# XBee_v1.net
KiCad netlist of a schematic drawn in EAGLE
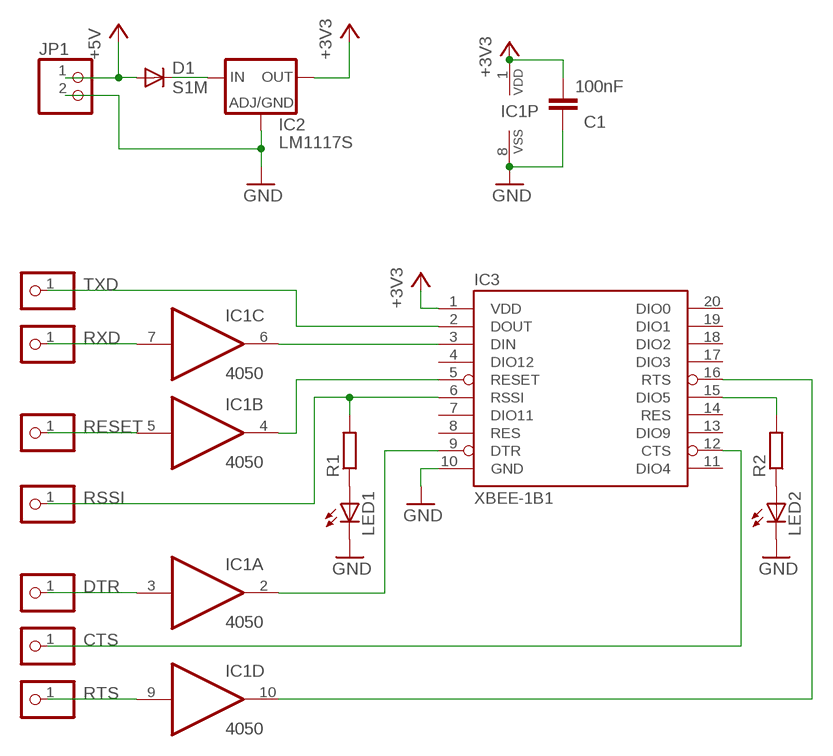
[diagram p0: schematic, sheet 1]

(export (version "E")
  (design (tool "Eeschema 10.0.6"))
  (components
    (comp (ref "C1")
      (value "100nF")
      (footprint "eagle-import:C0805K")
      (libsource (lib "eagle-import") (part "C-EUC0805K"))
    )
    (comp (ref "D1")
      (value "S1M")
      (footprint "eagle-import:DO-214AC")
      (libsource (lib "eagle-import") (part "S1M"))
    )
    (comp (ref "IC1")
      (value "4050")
      (footprint "eagle-import:SO16")
      (libsource (lib "eagle-import") (part "4050D"))
    )
    (comp (ref "IC2")
      (value "LM1117S")
      (footprint "eagle-import:SOT223")
      (libsource (lib "eagle-import") (part "LM1117S"))
    )
    (comp (ref "IC3")
      (value "XBEE-1B1")
      (footprint "eagle-import:XBEE-1")
      (libsource (lib "eagle-import") (part "XBEE-1B1"))
    )
    (comp (ref "JP1")
      (value "PINHD-1X2")
      (footprint "eagle-import:1X02")
      (libsource (lib "eagle-import") (part "PINHD-1X2"))
    )
    (comp (ref "JP2")
      (value "TXD")
      (footprint "eagle-import:1X01")
      (libsource (lib "eagle-import") (part "PINHD-1X1"))
    )
    (comp (ref "JP3")
      (value "RXD")
      (footprint "eagle-import:1X01")
      (libsource (lib "eagle-import") (part "PINHD-1X1"))
    )
    (comp (ref "JP4")
      (value "RST")
      (footprint "eagle-import:1X01")
      (libsource (lib "eagle-import") (part "PINHD-1X1"))
    )
    (comp (ref "JP5")
      (value "RSSI")
      (footprint "eagle-import:1X01")
      (libsource (lib "eagle-import") (part "PINHD-1X1"))
    )
    (comp (ref "JP6")
      (value "DTR")
      (footprint "eagle-import:1X01")
      (libsource (lib "eagle-import") (part "PINHD-1X1"))
    )
    (comp (ref "JP7")
      (value "CTS")
      (footprint "eagle-import:1X01")
      (libsource (lib "eagle-import") (part "PINHD-1X1"))
    )
    (comp (ref "JP8")
      (value "RTS")
      (footprint "eagle-import:1X01")
      (libsource (lib "eagle-import") (part "PINHD-1X1"))
    )
    (comp (ref "LED1")
      (value "LED3MM")
      (footprint "eagle-import:LED3MM")
      (libsource (lib "eagle-import") (part "LED3MM"))
    )
    (comp (ref "LED2")
      (value "LED3MM")
      (footprint "eagle-import:LED3MM")
      (libsource (lib "eagle-import") (part "LED3MM"))
    )
    (comp (ref "R1")
      (value "R-EU_R0805")
      (footprint "eagle-import:R0805")
      (libsource (lib "eagle-import") (part "R-EU_R0805"))
    )
    (comp (ref "R2")
      (value "R-EU_R0805")
      (footprint "eagle-import:R0805")
      (libsource (lib "eagle-import") (part "R-EU_R0805"))
    )
  )
  (nets
    (net (code "1") (name "+3V3") (class "Default")
      (node (ref "C1") (pin "2") (pinfunction "2_2") (pintype "passive"))
      (node (ref "IC1") (pin "1") (pinfunction "VDD_1") (pintype "power_in"))
      (node (ref "IC2") (pin "2") (pinfunction "OUT_2") (pintype "passive"))
      (node (ref "IC2") (pin "4") (pinfunction "OUT_4") (pintype "passive"))
      (node (ref "IC3") (pin "1") (pinfunction "VDD_1") (pintype "power_in"))
    )
    (net (code "2") (name "+5V") (class "Default")
      (node (ref "D1") (pin "A") (pinfunction "A_A") (pintype "passive"))
      (node (ref "JP1") (pin "1") (pinfunction "1_1") (pintype "passive"))
    )
    (net (code "3") (name "/CTS") (class "Default")
      (node (ref "IC3") (pin "12") (pinfunction "CTS_12") (pintype "output"))
      (node (ref "JP7") (pin "1") (pinfunction "1_1") (pintype "passive"))
    )
    (net (code "4") (name "/DTR") (class "Default")
      (node (ref "IC1") (pin "3") (pinfunction "I_3") (pintype "input"))
      (node (ref "JP6") (pin "1") (pinfunction "1_1") (pintype "passive"))
    )
    (net (code "5") (name "/RESET") (class "Default")
      (node (ref "IC1") (pin "5") (pinfunction "I_5") (pintype "input"))
      (node (ref "JP4") (pin "1") (pinfunction "1_1") (pintype "passive"))
    )
    (net (code "6") (name "/RSSI") (class "Default")
      (node (ref "IC3") (pin "6") (pinfunction "RSSI_6") (pintype "bidirectional"))
      (node (ref "JP5") (pin "1") (pinfunction "1_1") (pintype "passive"))
      (node (ref "R1") (pin "2") (pinfunction "2_2") (pintype "passive"))
    )
    (net (code "7") (name "/RTS") (class "Default")
      (node (ref "IC1") (pin "9") (pinfunction "I_9") (pintype "input"))
      (node (ref "JP8") (pin "1") (pinfunction "1_1") (pintype "passive"))
    )
    (net (code "8") (name "/RXD") (class "Default")
      (node (ref "IC1") (pin "7") (pinfunction "I_7") (pintype "input"))
      (node (ref "JP3") (pin "1") (pinfunction "1_1") (pintype "passive"))
    )
    (net (code "9") (name "/TXD") (class "Default")
      (node (ref "IC3") (pin "2") (pinfunction "DOUT_2") (pintype "output"))
      (node (ref "JP2") (pin "1") (pinfunction "1_1") (pintype "passive"))
    )
    (net (code "10") (name "GND") (class "Default")
      (node (ref "C1") (pin "1") (pinfunction "1_1") (pintype "passive"))
      (node (ref "IC1") (pin "8") (pinfunction "VSS_8") (pintype "power_in"))
      (node (ref "IC2") (pin "1") (pinfunction "ADJ_1") (pintype "input"))
      (node (ref "IC3") (pin "10") (pinfunction "GND_10") (pintype "power_in"))
      (node (ref "JP1") (pin "2") (pinfunction "2_2") (pintype "passive"))
      (node (ref "LED1") (pin "K") (pinfunction "C_K") (pintype "passive"))
      (node (ref "LED2") (pin "K") (pinfunction "C_K") (pintype "passive"))
    )
    (net (code "11") (name "Net-(IC1A-O)") (class "Default")
      (node (ref "IC1") (pin "2") (pinfunction "O_2") (pintype "output"))
      (node (ref "IC3") (pin "9") (pinfunction "DTR_9") (pintype "bidirectional"))
    )
    (net (code "12") (name "Net-(IC1B-O)") (class "Default")
      (node (ref "IC1") (pin "4") (pinfunction "O_4") (pintype "output"))
      (node (ref "IC3") (pin "5") (pinfunction "RESET_5") (pintype "input"))
    )
    (net (code "13") (name "Net-(IC1C-O)") (class "Default")
      (node (ref "IC1") (pin "6") (pinfunction "O_6") (pintype "output"))
      (node (ref "IC3") (pin "3") (pinfunction "DIN_3") (pintype "input"))
    )
    (net (code "14") (name "Net-(IC1D-O)") (class "Default")
      (node (ref "IC1") (pin "10") (pinfunction "O_10") (pintype "output"))
      (node (ref "IC3") (pin "16") (pinfunction "RTS_16") (pintype "input"))
    )
    (net (code "15") (name "Net-(IC2-IN)") (class "Default")
      (node (ref "D1") (pin "C") (pinfunction "C_C") (pintype "passive"))
      (node (ref "IC2") (pin "3") (pinfunction "IN_3") (pintype "input"))
    )
    (net (code "16") (name "Net-(IC3-DIO5)") (class "Default")
      (node (ref "IC3") (pin "15") (pinfunction "DIO5_15") (pintype "bidirectional"))
      (node (ref "R2") (pin "2") (pinfunction "2_2") (pintype "passive"))
    )
    (net (code "17") (name "Net-(LED1-PadA)") (class "Default")
      (node (ref "LED1") (pin "A") (pinfunction "A_A") (pintype "passive"))
      (node (ref "R1") (pin "1") (pinfunction "1_1") (pintype "passive"))
    )
    (net (code "18") (name "Net-(LED2-PadA)") (class "Default")
      (node (ref "LED2") (pin "A") (pinfunction "A_A") (pintype "passive"))
      (node (ref "R2") (pin "1") (pinfunction "1_1") (pintype "passive"))
    )
    (net (code "19") (name "unconnected-(IC3-DIO0-Pad20)") (class "Default")
      (node (ref "IC3") (pin "20") (pinfunction "DIO0_20") (pintype "bidirectional"))
    )
    (net (code "20") (name "unconnected-(IC3-DIO1-Pad19)") (class "Default")
      (node (ref "IC3") (pin "19") (pinfunction "DIO1_19") (pintype "bidirectional"))
    )
    (net (code "21") (name "unconnected-(IC3-DIO2-Pad18)") (class "Default")
      (node (ref "IC3") (pin "18") (pinfunction "DIO2_18") (pintype "bidirectional"))
    )
    (net (code "22") (name "unconnected-(IC3-DIO3-Pad17)") (class "Default")
      (node (ref "IC3") (pin "17") (pinfunction "DIO3_17") (pintype "bidirectional"))
    )
    (net (code "23") (name "unconnected-(IC3-DIO4-Pad11)") (class "Default")
      (node (ref "IC3") (pin "11") (pinfunction "DIO4_11") (pintype "bidirectional"))
    )
    (net (code "24") (name "unconnected-(IC3-DIO9-Pad13)") (class "Default")
      (node (ref "IC3") (pin "13") (pinfunction "DIO9_13") (pintype "bidirectional"))
    )
    (net (code "25") (name "unconnected-(IC3-DIO11-Pad7)") (class "Default")
      (node (ref "IC3") (pin "7") (pinfunction "DIO11_7") (pintype "bidirectional"))
    )
    (net (code "26") (name "unconnected-(IC3-DIO12-Pad4)") (class "Default")
      (node (ref "IC3") (pin "4") (pinfunction "DIO12_4") (pintype "bidirectional"))
    )
    (net (code "27") (name "unconnected-(IC3-RES-Pad8)") (class "Default")
      (node (ref "IC3") (pin "8") (pinfunction "RES_8") (pintype "bidirectional"))
    )
    (net (code "28") (name "unconnected-(IC3-RES-Pad14)") (class "Default")
      (node (ref "IC3") (pin "14") (pinfunction "RES_14") (pintype "bidirectional"))
    )
  )
)
